# Oscillator.net
KiCad netlist of a schematic drawn in Altium Designer
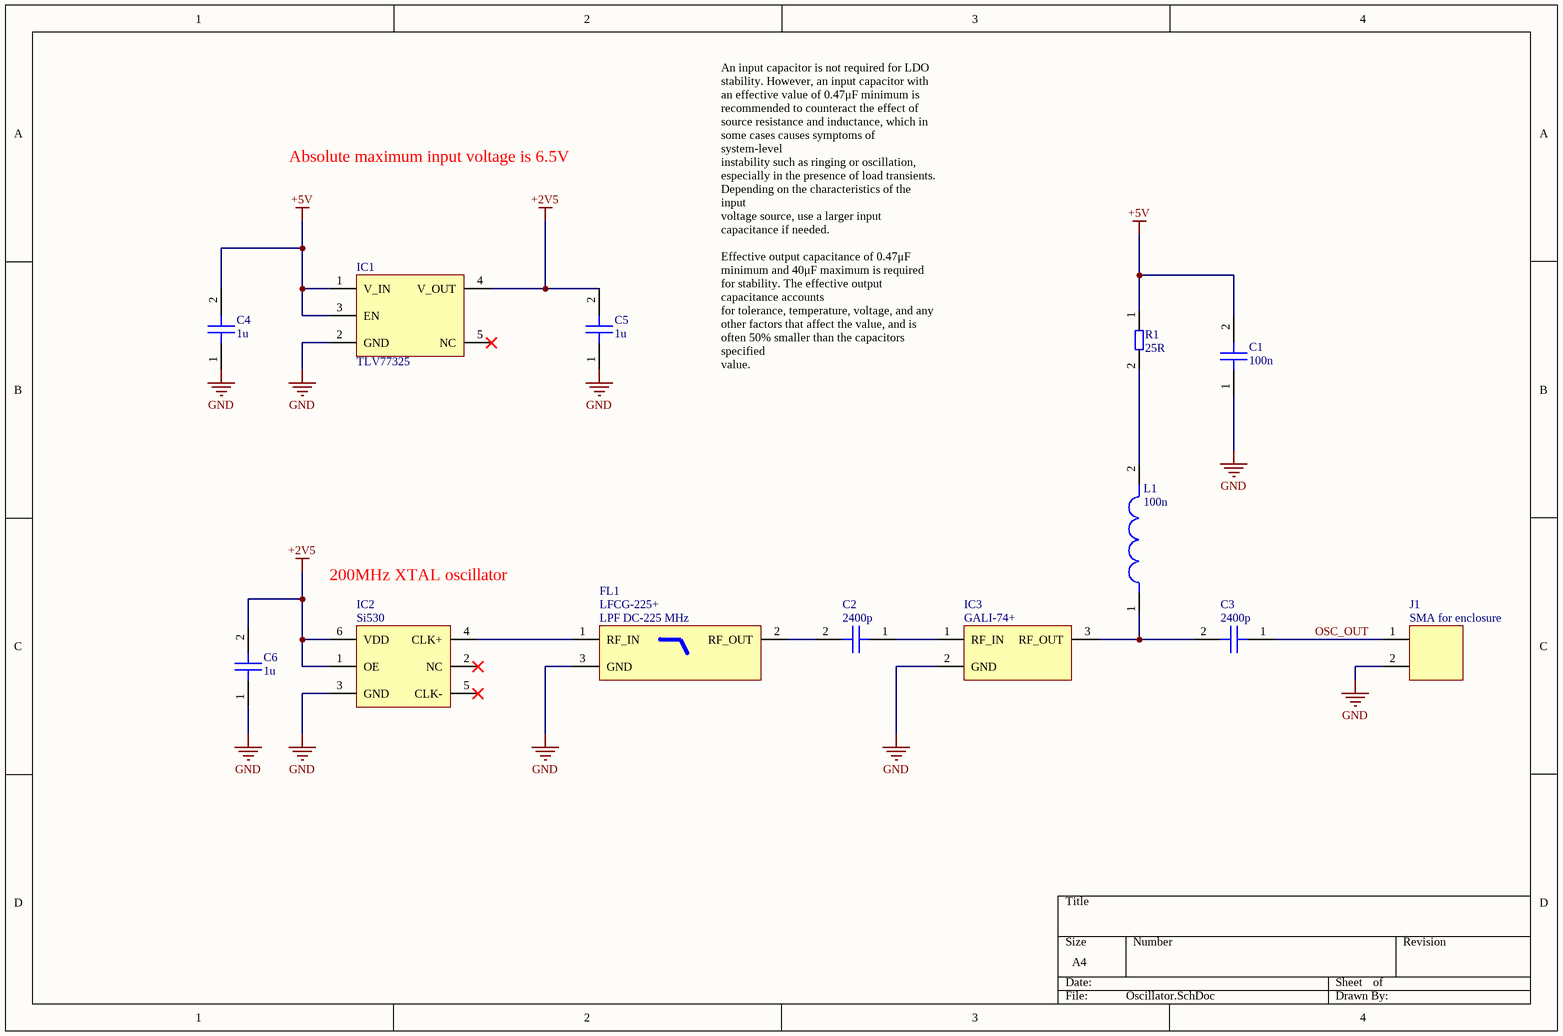
[diagram p0: Oscillator.SchDoc]

(export (version "E")
  (design (tool "Eeschema 10.0.6"))
  (components
    (comp (ref "C1")
      (value "100n")
      (footprint "0603_CAP")
      (libsource (lib "Radolovic_SCH_Library") (part "CAP_0603_generic"))
    )
    (comp (ref "C2")
      (value "2400p")
      (footprint "0603_CAP")
      (libsource (lib "Radolovic_SCH_Library") (part "CAP_0603_generic"))
    )
    (comp (ref "C3")
      (value "2400p")
      (footprint "0603_CAP")
      (libsource (lib "Radolovic_SCH_Library") (part "CAP_0603_generic"))
    )
    (comp (ref "C4")
      (value "1u")
      (footprint "0603_CAP")
      (libsource (lib "Radolovic_SCH_Library") (part "CAP_0603_generic"))
    )
    (comp (ref "C5")
      (value "1u")
      (footprint "0603_CAP")
      (libsource (lib "Radolovic_SCH_Library") (part "CAP_0603_generic"))
    )
    (comp (ref "C6")
      (value "1u")
      (footprint "0603_CAP")
      (libsource (lib "Radolovic_SCH_Library") (part "CAP_0603_generic"))
    )
    (comp (ref "FL1")
      (value "LFCG-225+")
      (description "LFCG-225+ Low Pass Filter")
      (libsource (lib "Radolovic_SCH_Library") (part "FL_LFCG-225+_MINI_CIRCUITS"))
    )
    (comp (ref "IC1")
      (value "TLV77325")
      (footprint "IC_TLV77325PDBVR_TEXAS_INSTRUMENTS")
      (description "LDO Voltage Regulators 300-mA high-PSRR low -IQ low-dropout regulator")
      (libsource (lib "Radolovic_SCH_Library") (part "IC_TLV77325_TEXAS_INSTRUMENTS"))
    )
    (comp (ref "IC2")
      (value "Si530")
      (footprint "IC_530FC200M000DG")
      (description "530FC200M000DG")
      (libsource (lib "Radolovic_SCH_Library") (part "IC_SI530_SILICON_LABS"))
    )
    (comp (ref "IC3")
      (value "GALI-74+")
      (footprint "IC_GALI74+_MINI_CIRCUITS")
      (description "RF Amplifier ML AMPL / SURF MT / RoHS")
      (libsource (lib "Radolovic_SCH_Library") (part "IC_GALI74+_MINI_CIRCUITS"))
    )
    (comp (ref "J1")
      (value "SMA for enclosure")
      (libsource (lib "Radolovic_SCH_Library") (part "HEADER_1x2_0.254MM"))
    )
    (comp (ref "L1")
      (value "100n")
      (footprint "0603_CAP")
      (libsource (lib "Radolovic_SCH_Library") (part "IND_air_0603_generic"))
    )
    (comp (ref "R1")
      (value "25R")
      (footprint "0603_RESISTOR")
      (description "3/4W")
      (libsource (lib "Radolovic_SCH_Library") (part "RES_0603_generic"))
    )
  )
  (nets
    (net (code "1") (name "+2V5") (class "Default")
      (node (ref "C5") (pin "2") (pintype "passive"))
      (node (ref "C6") (pin "2") (pintype "passive"))
      (node (ref "IC1") (pin "4") (pinfunction "V_OUT_4") (pintype "passive"))
      (node (ref "IC2") (pin "1") (pinfunction "OE_1") (pintype "passive"))
      (node (ref "IC2") (pin "6") (pinfunction "VDD_6") (pintype "passive"))
    )
    (net (code "2") (name "+5V") (class "Default")
      (node (ref "C1") (pin "2") (pintype "passive"))
      (node (ref "C4") (pin "2") (pintype "passive"))
      (node (ref "IC1") (pin "1") (pinfunction "V_IN_1") (pintype "passive"))
      (node (ref "IC1") (pin "3") (pinfunction "EN_3") (pintype "passive"))
      (node (ref "R1") (pin "1") (pintype "passive"))
    )
    (net (code "3") (name "/OSC_OUT") (class "Default")
      (node (ref "C3") (pin "1") (pintype "passive"))
      (node (ref "J1") (pin "1") (pintype "passive"))
    )
    (net (code "4") (name "GND") (class "Default")
      (node (ref "C1") (pin "1") (pintype "passive"))
      (node (ref "C4") (pin "1") (pintype "passive"))
      (node (ref "C5") (pin "1") (pintype "passive"))
      (node (ref "C6") (pin "1") (pintype "passive"))
      (node (ref "FL1") (pin "3") (pinfunction "GND_3") (pintype "passive"))
      (node (ref "IC1") (pin "2") (pinfunction "GND_2") (pintype "passive"))
      (node (ref "IC2") (pin "3") (pinfunction "GND_3") (pintype "passive"))
      (node (ref "IC3") (pin "2") (pinfunction "GND_2") (pintype "passive"))
      (node (ref "J1") (pin "2") (pintype "passive"))
    )
    (net (code "5") (name "Net-(FL1-RF_IN)") (class "Default")
      (node (ref "FL1") (pin "1") (pinfunction "RF_IN_1") (pintype "passive"))
      (node (ref "IC2") (pin "4") (pinfunction "CLK+_4") (pintype "passive"))
    )
    (net (code "6") (name "Net-(FL1-RF_OUT)") (class "Default")
      (node (ref "C2") (pin "2") (pintype "passive"))
      (node (ref "FL1") (pin "2") (pinfunction "RF_OUT_2") (pintype "passive"))
    )
    (net (code "7") (name "Net-(IC3-RF_IN)") (class "Default")
      (node (ref "C2") (pin "1") (pintype "passive"))
      (node (ref "IC3") (pin "1") (pinfunction "RF_IN_1") (pintype "passive"))
    )
    (net (code "8") (name "Net-(IC3-RF_OUT)") (class "Default")
      (node (ref "C3") (pin "2") (pintype "passive"))
      (node (ref "IC3") (pin "3") (pinfunction "RF_OUT_3") (pintype "passive"))
      (node (ref "L1") (pin "1") (pintype "passive"))
    )
    (net (code "9") (name "Net-(L1-Pad2)") (class "Default")
      (node (ref "L1") (pin "2") (pintype "passive"))
      (node (ref "R1") (pin "2") (pintype "passive"))
    )
    (net (code "10") (name "unconnected-(IC1-NC-Pad5)") (class "Default")
      (node (ref "IC1") (pin "5") (pinfunction "NC_5") (pintype "passive+no_connect"))
    )
    (net (code "11") (name "unconnected-(IC2-CLK--Pad5)") (class "Default")
      (node (ref "IC2") (pin "5") (pinfunction "CLK-_5") (pintype "passive+no_connect"))
    )
    (net (code "12") (name "unconnected-(IC2-NC-Pad2)") (class "Default")
      (node (ref "IC2") (pin "2") (pinfunction "NC_2") (pintype "passive+no_connect"))
    )
  )
)
